# Ethernet2_RMII.net
KiCad netlist of a schematic drawn in Altium Designer
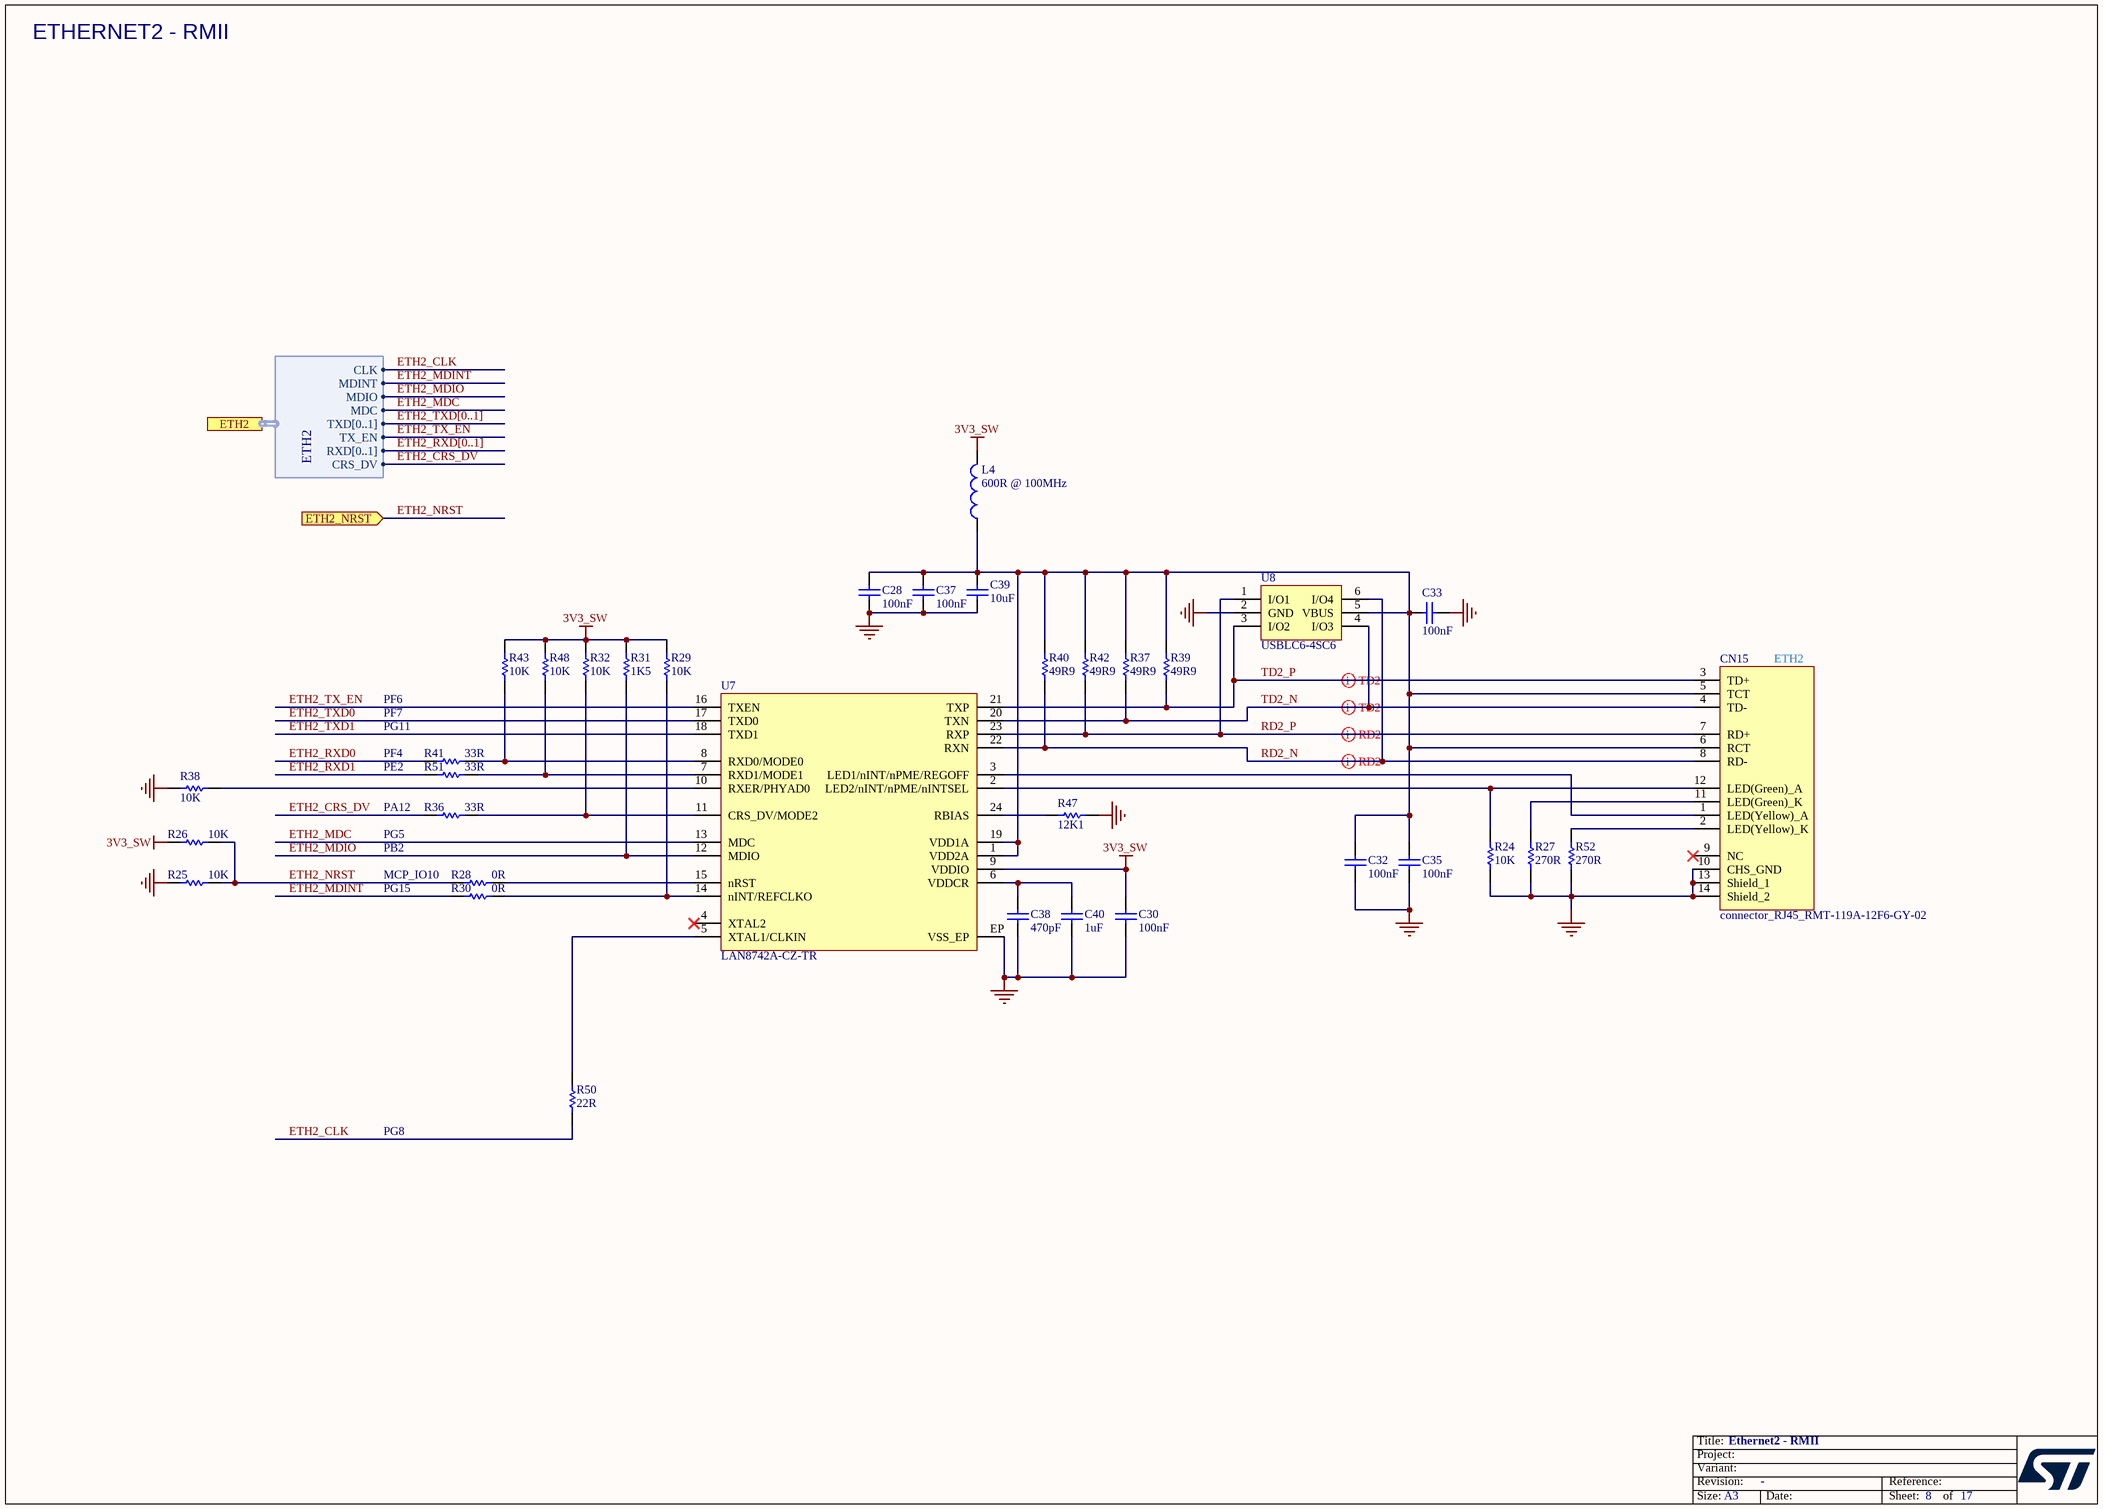
[diagram p0: Ethernet2_RMII.SchDoc]

(export (version "E")
  (design (tool "Eeschema 10.0.6"))
  (components
    (comp (ref "C28")
      (value "100nF")
      (footprint "C0402")
      (description "Capacitor, MLCC, 100nF, 16V, X7R, +/-10%, 0402, T=0.5mm")
      (fields
        (field (name "INTERNAL_PART_NUMBER") "MCD-00006")
        (field (name "MANUFACTURER_PART_NUMBER") "CC0402KRX7R7BB104")
      )
      (libsource (lib "MCD_PARTS_database") (part "Capacitor"))
    )
    (comp (ref "C30")
      (value "100nF")
      (footprint "C0402")
      (description "Capacitor, MLCC, 100nF, 16V, X7R, +/-10%, 0402, T=0.5mm")
      (fields
        (field (name "INTERNAL_PART_NUMBER") "MCD-00006")
        (field (name "MANUFACTURER_PART_NUMBER") "CC0402KRX7R7BB104")
      )
      (libsource (lib "MCD_PARTS_database") (part "Capacitor"))
    )
    (comp (ref "C32")
      (value "100nF")
      (footprint "C0402")
      (description "Capacitor, MLCC, 100nF, 16V, X7R, +/-10%, 0402, T=0.5mm")
      (fields
        (field (name "INTERNAL_PART_NUMBER") "MCD-00006")
        (field (name "MANUFACTURER_PART_NUMBER") "CC0402KRX7R7BB104")
      )
      (libsource (lib "MCD_PARTS_database") (part "Capacitor"))
    )
    (comp (ref "C33")
      (value "100nF")
      (footprint "C0402")
      (description "Capacitor, MLCC, 100nF, 16V, X7R, +/-10%, 0402, T=0.5mm")
      (fields
        (field (name "INTERNAL_PART_NUMBER") "MCD-00006")
        (field (name "MANUFACTURER_PART_NUMBER") "CC0402KRX7R7BB104")
      )
      (libsource (lib "MCD_PARTS_database") (part "Capacitor"))
    )
    (comp (ref "C35")
      (value "100nF")
      (footprint "C0402")
      (description "Capacitor, MLCC, 100nF, 16V, X7R, +/-10%, 0402, T=0.5mm")
      (fields
        (field (name "INTERNAL_PART_NUMBER") "MCD-00006")
        (field (name "MANUFACTURER_PART_NUMBER") "CC0402KRX7R7BB104")
      )
      (libsource (lib "MCD_PARTS_database") (part "Capacitor"))
    )
    (comp (ref "C37")
      (value "100nF")
      (footprint "C0402")
      (description "Capacitor, MLCC, 100nF, 16V, X7R, +/-10%, 0402, T=0.5mm")
      (fields
        (field (name "INTERNAL_PART_NUMBER") "MCD-00006")
        (field (name "MANUFACTURER_PART_NUMBER") "CC0402KRX7R7BB104")
      )
      (libsource (lib "MCD_PARTS_database") (part "Capacitor"))
    )
    (comp (ref "C38")
      (value "470pF")
      (footprint "C0402")
      (description "Capacitor, MLCC, 470pF, 50V, NPO, +/-5%, 0402, T=0.5mm")
      (fields
        (field (name "INTERNAL_PART_NUMBER") "MCD-00724")
        (field (name "MANUFACTURER_PART_NUMBER") "CC0402JRNPO9BN471")
      )
      (libsource (lib "MCD_PARTS_database") (part "Capacitor"))
    )
    (comp (ref "C39")
      (value "10uF")
      (footprint "C0603")
      (description "Capacitor, MLCC, 10uF, 10V, X5R, +/-10%, 0603, T=0.8mm")
      (fields
        (field (name "INTERNAL_PART_NUMBER") "MCD-00099")
        (field (name "MANUFACTURER_PART_NUMBER") "GRM188R61A106KE69D")
      )
      (libsource (lib "MCD_PARTS_database") (part "Capacitor"))
    )
    (comp (ref "C40")
      (value "1uF")
      (footprint "C0201_MURATA_GRM033_H0P3")
      (description "Capacitor, MLCC, 1uF, 6.3V, X5R, +/-20%, 0201, T=0,3mm")
      (fields
        (field (name "INTERNAL_PART_NUMBER") "MCD-02377")
        (field (name "MANUFACTURER_PART_NUMBER") "GRM033R60J105MEA2")
      )
      (libsource (lib "MCD_PARTS_database") (part "Capacitor"))
    )
    (comp (ref "CN15")
      (value "connector_RJ45_RMT-119A-12F6-GY-02")
      (footprint "CON_RJ45_PHC_RMT-119A-12F6-GY-02")
      (description "connector_RJ45, 10/100 Ethernet integrated MAG with integrate Green and Yellow LED, T= 13.61mm")
      (fields (field (name "INTERNAL_PART_NUMBER") "MCD-02475") (field (name "MANUFACTURER") "PENGHUI"))
      (libsource (lib "MCD_PARTS_database") (part "RJ45_RTS-119A-12F6-GY-02"))
    )
    (comp (ref "L4")
      (value "600R @ 100MHz")
      (footprint "L0603")
      (description "Ferrite bead, 600R @1 00MHz, +/-25%, 350mA, 0R5, 0603, T=0.8mm")
      (fields
        (field (name "INTERNAL_PART_NUMBER") "MCD-00047")
        (field (name "MANUFACTURER_PART_NUMBER") "FCM1608KF-601T03")
      )
      (libsource (lib "MCD_PARTS_database") (part "BEAD"))
    )
    (comp (ref "R24")
      (value "10K")
      (footprint "R0402")
      (description "Resistor, 10K, 0402, +/-1%, 1/16W")
      (fields
        (field (name "INTERNAL_PART_NUMBER") "MCD-00053")
        (field (name "MANUFACTURER_PART_NUMBER") "RC0402FR-0710KL")
      )
      (libsource (lib "MCD_PARTS_database") (part "Resistor"))
    )
    (comp (ref "R25")
      (value "10K")
      (footprint "R0402")
      (description "Resistor, 10K, 0402, +/-1%, 1/16W")
      (fields
        (field (name "INTERNAL_PART_NUMBER") "MCD-00053")
        (field (name "MANUFACTURER_PART_NUMBER") "RC0402FR-0710KL")
      )
      (libsource (lib "MCD_PARTS_database") (part "Resistor"))
    )
    (comp (ref "R26")
      (value "10K")
      (footprint "R0402")
      (description "Resistor, 10K, 0402, +/-1%, 1/16W")
      (fields
        (field (name "INTERNAL_PART_NUMBER") "MCD-00053")
        (field (name "MANUFACTURER_PART_NUMBER") "RC0402FR-0710KL")
      )
      (libsource (lib "MCD_PARTS_database") (part "Resistor"))
    )
    (comp (ref "R27")
      (value "270R")
      (footprint "R0402")
      (description "Resistor, 270R, 0402, +/-1%, 1/16W")
      (fields
        (field (name "INTERNAL_PART_NUMBER") "MCD-00441")
        (field (name "MANUFACTURER_PART_NUMBER") "RC0402FR-07270RL")
      )
      (libsource (lib "MCD_PARTS_database") (part "Resistor"))
    )
    (comp (ref "R28")
      (value "0R")
      (footprint "R0402")
      (description "Resistor, 0R, 0402, +/-5%, 1/16W")
      (fields (field (name "INTERNAL_PART_NUMBER") "MCD-00052") (field (name "MANUFACTURER") "YAGEO"))
      (libsource (lib "MCD_PARTS_database") (part "Resistor"))
    )
    (comp (ref "R29")
      (value "10K")
      (footprint "R0402")
      (description "Resistor, 10K, 0402, +/-1%, 1/16W")
      (fields
        (field (name "INTERNAL_PART_NUMBER") "MCD-00053")
        (field (name "MANUFACTURER_PART_NUMBER") "RC0402FR-0710KL")
      )
      (libsource (lib "MCD_PARTS_database") (part "Resistor"))
    )
    (comp (ref "R30")
      (value "0R")
      (footprint "R0402")
      (description "Resistor, 0R, 0402, +/-5%, 1/16W")
      (fields
        (field (name "INTERNAL_PART_NUMBER") "MCD-00052")
        (field (name "MANUFACTURER_PART_NUMBER") "RC0402JR-070RL")
      )
      (libsource (lib "MCD_PARTS_database") (part "Resistor"))
    )
    (comp (ref "R31")
      (value "1K5")
      (footprint "R0402")
      (description "Resistor, 1K5, 0402, +/-1%, 1/16W")
      (fields
        (field (name "INTERNAL_PART_NUMBER") "MCD-00068")
        (field (name "MANUFACTURER_PART_NUMBER") "RC0402FR-071K5L")
      )
      (libsource (lib "MCD_PARTS_database") (part "Resistor"))
    )
    (comp (ref "R32")
      (value "10K")
      (footprint "R0402")
      (description "Resistor, 10K, 0402, +/-1%, 1/16W")
      (fields
        (field (name "INTERNAL_PART_NUMBER") "MCD-00053")
        (field (name "MANUFACTURER_PART_NUMBER") "RC0402FR-0710KL")
      )
      (libsource (lib "MCD_PARTS_database") (part "Resistor"))
    )
    (comp (ref "R36")
      (value "33R")
      (footprint "R0402")
      (description "Resistor, 33R, 0402, +/-1%, 1/16W")
      (fields
        (field (name "INTERNAL_PART_NUMBER") "MCD-00455")
        (field (name "MANUFACTURER_PART_NUMBER") "RC0402FR-0733RL")
      )
      (libsource (lib "MCD_PARTS_database") (part "Resistor"))
    )
    (comp (ref "R37")
      (value "49R9")
      (footprint "R0402")
      (description "Resistor, 49R9, 0402, +/-1%, 1/16W")
      (fields
        (field (name "INTERNAL_PART_NUMBER") "MCD-00565")
        (field (name "MANUFACTURER_PART_NUMBER") "RC0402FR-0749R9L")
      )
      (libsource (lib "MCD_PARTS_database") (part "Resistor"))
    )
    (comp (ref "R38")
      (value "10K")
      (footprint "R0402")
      (description "Resistor, 10K, 0402, +/-1%, 1/16W")
      (fields
        (field (name "INTERNAL_PART_NUMBER") "MCD-00053")
        (field (name "MANUFACTURER_PART_NUMBER") "RC0402FR-0710KL")
      )
      (libsource (lib "MCD_PARTS_database") (part "Resistor"))
    )
    (comp (ref "R39")
      (value "49R9")
      (footprint "R0402")
      (description "Resistor, 49R9, 0402, +/-1%, 1/16W")
      (fields
        (field (name "INTERNAL_PART_NUMBER") "MCD-00565")
        (field (name "MANUFACTURER_PART_NUMBER") "RC0402FR-0749R9L")
      )
      (libsource (lib "MCD_PARTS_database") (part "Resistor"))
    )
    (comp (ref "R40")
      (value "49R9")
      (footprint "R0402")
      (description "Resistor, 49R9, 0402, +/-1%, 1/16W")
      (fields
        (field (name "INTERNAL_PART_NUMBER") "MCD-00565")
        (field (name "MANUFACTURER_PART_NUMBER") "RC0402FR-0749R9L")
      )
      (libsource (lib "MCD_PARTS_database") (part "Resistor"))
    )
    (comp (ref "R41")
      (value "33R")
      (footprint "R0402")
      (description "Resistor, 33R, 0402, +/-1%, 1/16W")
      (fields
        (field (name "INTERNAL_PART_NUMBER") "MCD-00455")
        (field (name "MANUFACTURER_PART_NUMBER") "RC0402FR-0733RL")
      )
      (libsource (lib "MCD_PARTS_database") (part "Resistor"))
    )
    (comp (ref "R42")
      (value "49R9")
      (footprint "R0402")
      (description "Resistor, 49R9, 0402, +/-1%, 1/16W")
      (fields
        (field (name "INTERNAL_PART_NUMBER") "MCD-00565")
        (field (name "MANUFACTURER_PART_NUMBER") "RC0402FR-0749R9L")
      )
      (libsource (lib "MCD_PARTS_database") (part "Resistor"))
    )
    (comp (ref "R43")
      (value "10K")
      (footprint "R0402")
      (description "Resistor, 10K, 0402, +/-1%, 1/16W")
      (fields
        (field (name "INTERNAL_PART_NUMBER") "MCD-00053")
        (field (name "MANUFACTURER_PART_NUMBER") "RC0402FR-0710KL")
      )
      (libsource (lib "MCD_PARTS_database") (part "Resistor"))
    )
    (comp (ref "R47")
      (value "12K1")
      (footprint "R0402")
      (description "Resistor, 12K1, 0402, +/-1%, 1/16W")
      (fields
        (field (name "INTERNAL_PART_NUMBER") "MCD-00723")
        (field (name "MANUFACTURER_PART_NUMBER") "RC0402FR-0712K1L")
      )
      (libsource (lib "MCD_PARTS_database") (part "Resistor"))
    )
    (comp (ref "R48")
      (value "10K")
      (footprint "R0402")
      (description "Resistor, 10K, 0402, +/-1%, 1/16W")
      (fields
        (field (name "INTERNAL_PART_NUMBER") "MCD-00053")
        (field (name "MANUFACTURER_PART_NUMBER") "RC0402FR-0710KL")
      )
      (libsource (lib "MCD_PARTS_database") (part "Resistor"))
    )
    (comp (ref "R50")
      (value "22R")
      (footprint "R0402")
      (description "Resistor, 22R, 0402, +/-1%, 1/16W")
      (fields
        (field (name "INTERNAL_PART_NUMBER") "MCD-00189")
        (field (name "MANUFACTURER_PART_NUMBER") "RC0402FR-0722RL")
      )
      (libsource (lib "MCD_PARTS_database") (part "Resistor"))
    )
    (comp (ref "R51")
      (value "33R")
      (footprint "R0402")
      (description "Resistor, 33R, 0402, +/-1%, 1/16W")
      (fields
        (field (name "INTERNAL_PART_NUMBER") "MCD-00455")
        (field (name "MANUFACTURER_PART_NUMBER") "RC0402FR-0733RL")
      )
      (libsource (lib "MCD_PARTS_database") (part "Resistor"))
    )
    (comp (ref "R52")
      (value "270R")
      (footprint "R0402")
      (description "Resistor, 270R, 0402, +/-1%, 1/16W")
      (fields
        (field (name "INTERNAL_PART_NUMBER") "MCD-00441")
        (field (name "MANUFACTURER_PART_NUMBER") "RC0402FR-07270RL")
      )
      (libsource (lib "MCD_PARTS_database") (part "Resistor"))
    )
    (comp (ref "U7")
      (value "LAN8742A-CZ-TR")
      (footprint "ICC_VQFN24-EPAD_4X4_P050")
      (description "10/100M RMII Ethernet transceiver")
      (fields (field (name "INTERNAL_PART_NUMBER") "MCD-00719") (field (name "MANUFACTURER") "MICROCHIP"))
      (libsource (lib "MCD_PARTS_database") (part "LAN8742A-CZ-TR"))
    )
    (comp (ref "U8")
      (value "USBLC6-4SC6")
      (footprint "ESD_SOT23-6L")
      (description "Very low capacitance ESD protection , 4 lines")
      (fields
        (field (name "INTERNAL_PART_NUMBER") "MCD-00250")
        (field (name "MANUFACTURER") "STMICROELECTRONICS")
      )
      (libsource (lib "MCD_PARTS_database") (part "USBLC6-4SC6"))
    )
  )
  (nets
    (net (code "2") (name "/ETH2_CLK") (class "Default")
      (node (ref "R50") (pin "1") (pinfunction "1_1") (pintype "passive"))
    )
    (net (code "3") (name "/ETH2_CRS_DV") (class "Default")
      (node (ref "R36") (pin "1") (pinfunction "1_1") (pintype "passive"))
    )
    (net (code "4") (name "/ETH2_MDC") (class "Default")
      (node (ref "U7") (pin "13") (pinfunction "MDC_13") (pintype "passive"))
    )
    (net (code "5") (name "/ETH2_MDINT") (class "Default")
      (node (ref "R30") (pin "1") (pinfunction "1_1") (pintype "passive"))
    )
    (net (code "6") (name "/ETH2_MDIO") (class "Default")
      (node (ref "R31") (pin "1") (pinfunction "1_1") (pintype "passive"))
      (node (ref "U7") (pin "12") (pinfunction "MDIO_12") (pintype "passive"))
    )
    (net (code "7") (name "/ETH2_NRST") (class "Default")
      (node (ref "R25") (pin "1") (pinfunction "1_1") (pintype "passive"))
      (node (ref "R26") (pin "1") (pinfunction "1_1") (pintype "passive"))
      (node (ref "R28") (pin "1") (pinfunction "1_1") (pintype "passive"))
    )
    (net (code "8") (name "/ETH2_RXD0") (class "Default")
      (node (ref "R41") (pin "1") (pinfunction "1_1") (pintype "passive"))
    )
    (net (code "9") (name "/ETH2_RXD1") (class "Default")
      (node (ref "R51") (pin "1") (pinfunction "1_1") (pintype "passive"))
    )
    (net (code "11") (name "/ETH2_TXD0") (class "Default")
      (node (ref "U7") (pin "17") (pinfunction "TXD0_17") (pintype "passive"))
    )
    (net (code "12") (name "/ETH2_TXD1") (class "Default")
      (node (ref "U7") (pin "18") (pinfunction "TXD1_18") (pintype "passive"))
    )
    (net (code "13") (name "/ETH2_TX_EN") (class "Default")
      (node (ref "U7") (pin "16") (pinfunction "TXEN_16") (pintype "passive"))
    )
    (net (code "15") (name "/RD2_N") (class "Default")
      (node (ref "CN15") (pin "8") (pinfunction "RD-_8") (pintype "passive"))
      (node (ref "R40") (pin "1") (pinfunction "1_1") (pintype "passive"))
      (node (ref "U7") (pin "22") (pinfunction "RXN_22") (pintype "passive"))
      (node (ref "U8") (pin "6") (pinfunction "I/O4_6") (pintype "passive"))
    )
    (net (code "16") (name "/RD2_P") (class "Default")
      (node (ref "CN15") (pin "7") (pinfunction "RD+_7") (pintype "passive"))
      (node (ref "R42") (pin "1") (pinfunction "1_1") (pintype "passive"))
      (node (ref "U7") (pin "23") (pinfunction "RXP_23") (pintype "passive"))
      (node (ref "U8") (pin "1") (pinfunction "I/O1_1") (pintype "passive"))
    )
    (net (code "17") (name "/TD2_N") (class "Default")
      (node (ref "CN15") (pin "4") (pinfunction "TD-_4") (pintype "passive"))
      (node (ref "R37") (pin "1") (pinfunction "1_1") (pintype "passive"))
      (node (ref "U7") (pin "20") (pinfunction "TXN_20") (pintype "passive"))
      (node (ref "U8") (pin "4") (pinfunction "I/O3_4") (pintype "passive"))
    )
    (net (code "18") (name "/TD2_P") (class "Default")
      (node (ref "CN15") (pin "3") (pinfunction "TD+_3") (pintype "passive"))
      (node (ref "R39") (pin "1") (pinfunction "1_1") (pintype "passive"))
      (node (ref "U7") (pin "21") (pinfunction "TXP_21") (pintype "passive"))
      (node (ref "U8") (pin "3") (pinfunction "I/O2_3") (pintype "passive"))
    )
    (net (code "19") (name "3V3_SW") (class "Default")
      (node (ref "C30") (pin "2") (pinfunction "2_2") (pintype "passive"))
      (node (ref "L4") (pin "2") (pinfunction "2_2") (pintype "passive"))
      (node (ref "R26") (pin "2") (pinfunction "2_2") (pintype "passive"))
      (node (ref "R29") (pin "2") (pinfunction "2_2") (pintype "passive"))
      (node (ref "R31") (pin "2") (pinfunction "2_2") (pintype "passive"))
      (node (ref "R32") (pin "2") (pinfunction "2_2") (pintype "passive"))
      (node (ref "R43") (pin "2") (pinfunction "2_2") (pintype "passive"))
      (node (ref "R48") (pin "2") (pinfunction "2_2") (pintype "passive"))
      (node (ref "U7") (pin "9") (pinfunction "VDDIO_9") (pintype "passive"))
    )
    (net (code "20") (name "GND") (class "Default")
      (node (ref "C28") (pin "1") (pinfunction "1_1") (pintype "passive"))
      (node (ref "C30") (pin "1") (pinfunction "1_1") (pintype "passive"))
      (node (ref "C32") (pin "1") (pinfunction "1_1") (pintype "passive"))
      (node (ref "C33") (pin "2") (pinfunction "2_2") (pintype "passive"))
      (node (ref "C35") (pin "1") (pinfunction "1_1") (pintype "passive"))
      (node (ref "C37") (pin "1") (pinfunction "1_1") (pintype "passive"))
      (node (ref "C38") (pin "1") (pinfunction "1_1") (pintype "passive"))
      (node (ref "C39") (pin "2") (pinfunction "2_2") (pintype "passive"))
      (node (ref "C40") (pin "1") (pinfunction "1_1") (pintype "passive"))
      (node (ref "CN15") (pin "10") (pinfunction "CHS_GND_10") (pintype "passive"))
      (node (ref "CN15") (pin "13") (pinfunction "Shield_1_13") (pintype "passive"))
      (node (ref "CN15") (pin "14") (pinfunction "Shield_2_14") (pintype "passive"))
      (node (ref "R24") (pin "1") (pinfunction "1_1") (pintype "passive"))
      (node (ref "R25") (pin "2") (pinfunction "2_2") (pintype "passive"))
      (node (ref "R27") (pin "1") (pinfunction "1_1") (pintype "passive"))
      (node (ref "R38") (pin "2") (pinfunction "2_2") (pintype "passive"))
      (node (ref "R47") (pin "2") (pinfunction "2_2") (pintype "passive"))
      (node (ref "R52") (pin "1") (pinfunction "1_1") (pintype "passive"))
      (node (ref "U7") (pin "EP") (pinfunction "VSS_EP_EP") (pintype "passive"))
      (node (ref "U8") (pin "2") (pinfunction "GND_2") (pintype "passive"))
    )
    (net (code "21") (name "Net-(CN15-LED(Green)_A)") (class "Default")
      (node (ref "CN15") (pin "12") (pinfunction "LED(Green)_A_12") (pintype "passive"))
      (node (ref "R24") (pin "2") (pinfunction "2_2") (pintype "passive"))
      (node (ref "U7") (pin "2") (pinfunction "LED2/nINT/nPME/nINTSEL_2") (pintype "passive"))
    )
    (net (code "22") (name "Net-(CN15-LED(Green)_K)") (class "Default")
      (node (ref "CN15") (pin "11") (pinfunction "LED(Green)_K_11") (pintype "passive"))
      (node (ref "R27") (pin "2") (pinfunction "2_2") (pintype "passive"))
    )
    (net (code "23") (name "Net-(CN15-LED(Yellow)_A)") (class "Default")
      (node (ref "CN15") (pin "1") (pinfunction "LED(Yellow)_A_1") (pintype "passive"))
      (node (ref "U7") (pin "3") (pinfunction "LED1/nINT/nPME/REGOFF_3") (pintype "passive"))
    )
    (net (code "24") (name "Net-(CN15-LED(Yellow)_K)") (class "Default")
      (node (ref "CN15") (pin "2") (pinfunction "LED(Yellow)_K_2") (pintype "passive"))
      (node (ref "R52") (pin "2") (pinfunction "2_2") (pintype "passive"))
    )
    (net (code "25") (name "Net-(CN15-RCT)") (class "Default")
      (node (ref "C28") (pin "2") (pinfunction "2_2") (pintype "passive"))
      (node (ref "C32") (pin "2") (pinfunction "2_2") (pintype "passive"))
      (node (ref "C33") (pin "1") (pinfunction "1_1") (pintype "passive"))
      (node (ref "C35") (pin "2") (pinfunction "2_2") (pintype "passive"))
      (node (ref "C37") (pin "2") (pinfunction "2_2") (pintype "passive"))
      (node (ref "C39") (pin "1") (pinfunction "1_1") (pintype "passive"))
      (node (ref "CN15") (pin "5") (pinfunction "TCT_5") (pintype "passive"))
      (node (ref "CN15") (pin "6") (pinfunction "RCT_6") (pintype "passive"))
      (node (ref "L4") (pin "1") (pinfunction "1_1") (pintype "passive"))
      (node (ref "R37") (pin "2") (pinfunction "2_2") (pintype "passive"))
      (node (ref "R39") (pin "2") (pinfunction "2_2") (pintype "passive"))
      (node (ref "R40") (pin "2") (pinfunction "2_2") (pintype "passive"))
      (node (ref "R42") (pin "2") (pinfunction "2_2") (pintype "passive"))
      (node (ref "U7") (pin "1") (pinfunction "VDD2A_1") (pintype "passive"))
      (node (ref "U7") (pin "19") (pinfunction "VDD1A_19") (pintype "passive"))
      (node (ref "U8") (pin "5") (pinfunction "VBUS_5") (pintype "passive"))
    )
    (net (code "26") (name "Net-(U7-CRS_DV{slash}MODE2)") (class "Default")
      (node (ref "R32") (pin "1") (pinfunction "1_1") (pintype "passive"))
      (node (ref "R36") (pin "2") (pinfunction "2_2") (pintype "passive"))
      (node (ref "U7") (pin "11") (pinfunction "CRS_DV/MODE2_11") (pintype "passive"))
    )
    (net (code "27") (name "Net-(U7-RBIAS)") (class "Default")
      (node (ref "R47") (pin "1") (pinfunction "1_1") (pintype "passive"))
      (node (ref "U7") (pin "24") (pinfunction "RBIAS_24") (pintype "passive"))
    )
    (net (code "28") (name "Net-(U7-RXD0{slash}MODE0)") (class "Default")
      (node (ref "R41") (pin "2") (pinfunction "2_2") (pintype "passive"))
      (node (ref "R43") (pin "1") (pinfunction "1_1") (pintype "passive"))
      (node (ref "U7") (pin "8") (pinfunction "RXD0/MODE0_8") (pintype "passive"))
    )
    (net (code "29") (name "Net-(U7-RXD1{slash}MODE1)") (class "Default")
      (node (ref "R48") (pin "1") (pinfunction "1_1") (pintype "passive"))
      (node (ref "R51") (pin "2") (pinfunction "2_2") (pintype "passive"))
      (node (ref "U7") (pin "7") (pinfunction "RXD1/MODE1_7") (pintype "passive"))
    )
    (net (code "30") (name "Net-(U7-RXER{slash}PHYAD0)") (class "Default")
      (node (ref "R38") (pin "1") (pinfunction "1_1") (pintype "passive"))
      (node (ref "U7") (pin "10") (pinfunction "RXER/PHYAD0_10") (pintype "passive"))
    )
    (net (code "31") (name "Net-(U7-VDDCR)") (class "Default")
      (node (ref "C38") (pin "2") (pinfunction "2_2") (pintype "passive"))
      (node (ref "C40") (pin "2") (pinfunction "2_2") (pintype "passive"))
      (node (ref "U7") (pin "6") (pinfunction "VDDCR_6") (pintype "passive"))
    )
    (net (code "32") (name "Net-(U7-XTAL1{slash}CLKIN)") (class "Default")
      (node (ref "R50") (pin "2") (pinfunction "2_2") (pintype "passive"))
      (node (ref "U7") (pin "5") (pinfunction "XTAL1/CLKIN_5") (pintype "passive"))
    )
    (net (code "33") (name "Net-(U7-nINT{slash}REFCLKO)") (class "Default")
      (node (ref "R29") (pin "1") (pinfunction "1_1") (pintype "passive"))
      (node (ref "R30") (pin "2") (pinfunction "2_2") (pintype "passive"))
      (node (ref "U7") (pin "14") (pinfunction "nINT/REFCLKO_14") (pintype "passive"))
    )
    (net (code "34") (name "Net-(U7-nRST)") (class "Default")
      (node (ref "R28") (pin "2") (pinfunction "2_2") (pintype "passive"))
      (node (ref "U7") (pin "15") (pinfunction "nRST_15") (pintype "passive"))
    )
    (net (code "35") (name "unconnected-(CN15-NC-Pad9)") (class "Default")
      (node (ref "CN15") (pin "9") (pinfunction "NC_9") (pintype "passive+no_connect"))
    )
    (net (code "36") (name "unconnected-(U7-XTAL2-Pad4)") (class "Default")
      (node (ref "U7") (pin "4") (pinfunction "XTAL2_4") (pintype "passive+no_connect"))
    )
  )
)
